# led_cube_4x4x8_v1.net
KiCad netlist of a schematic drawn in EAGLE
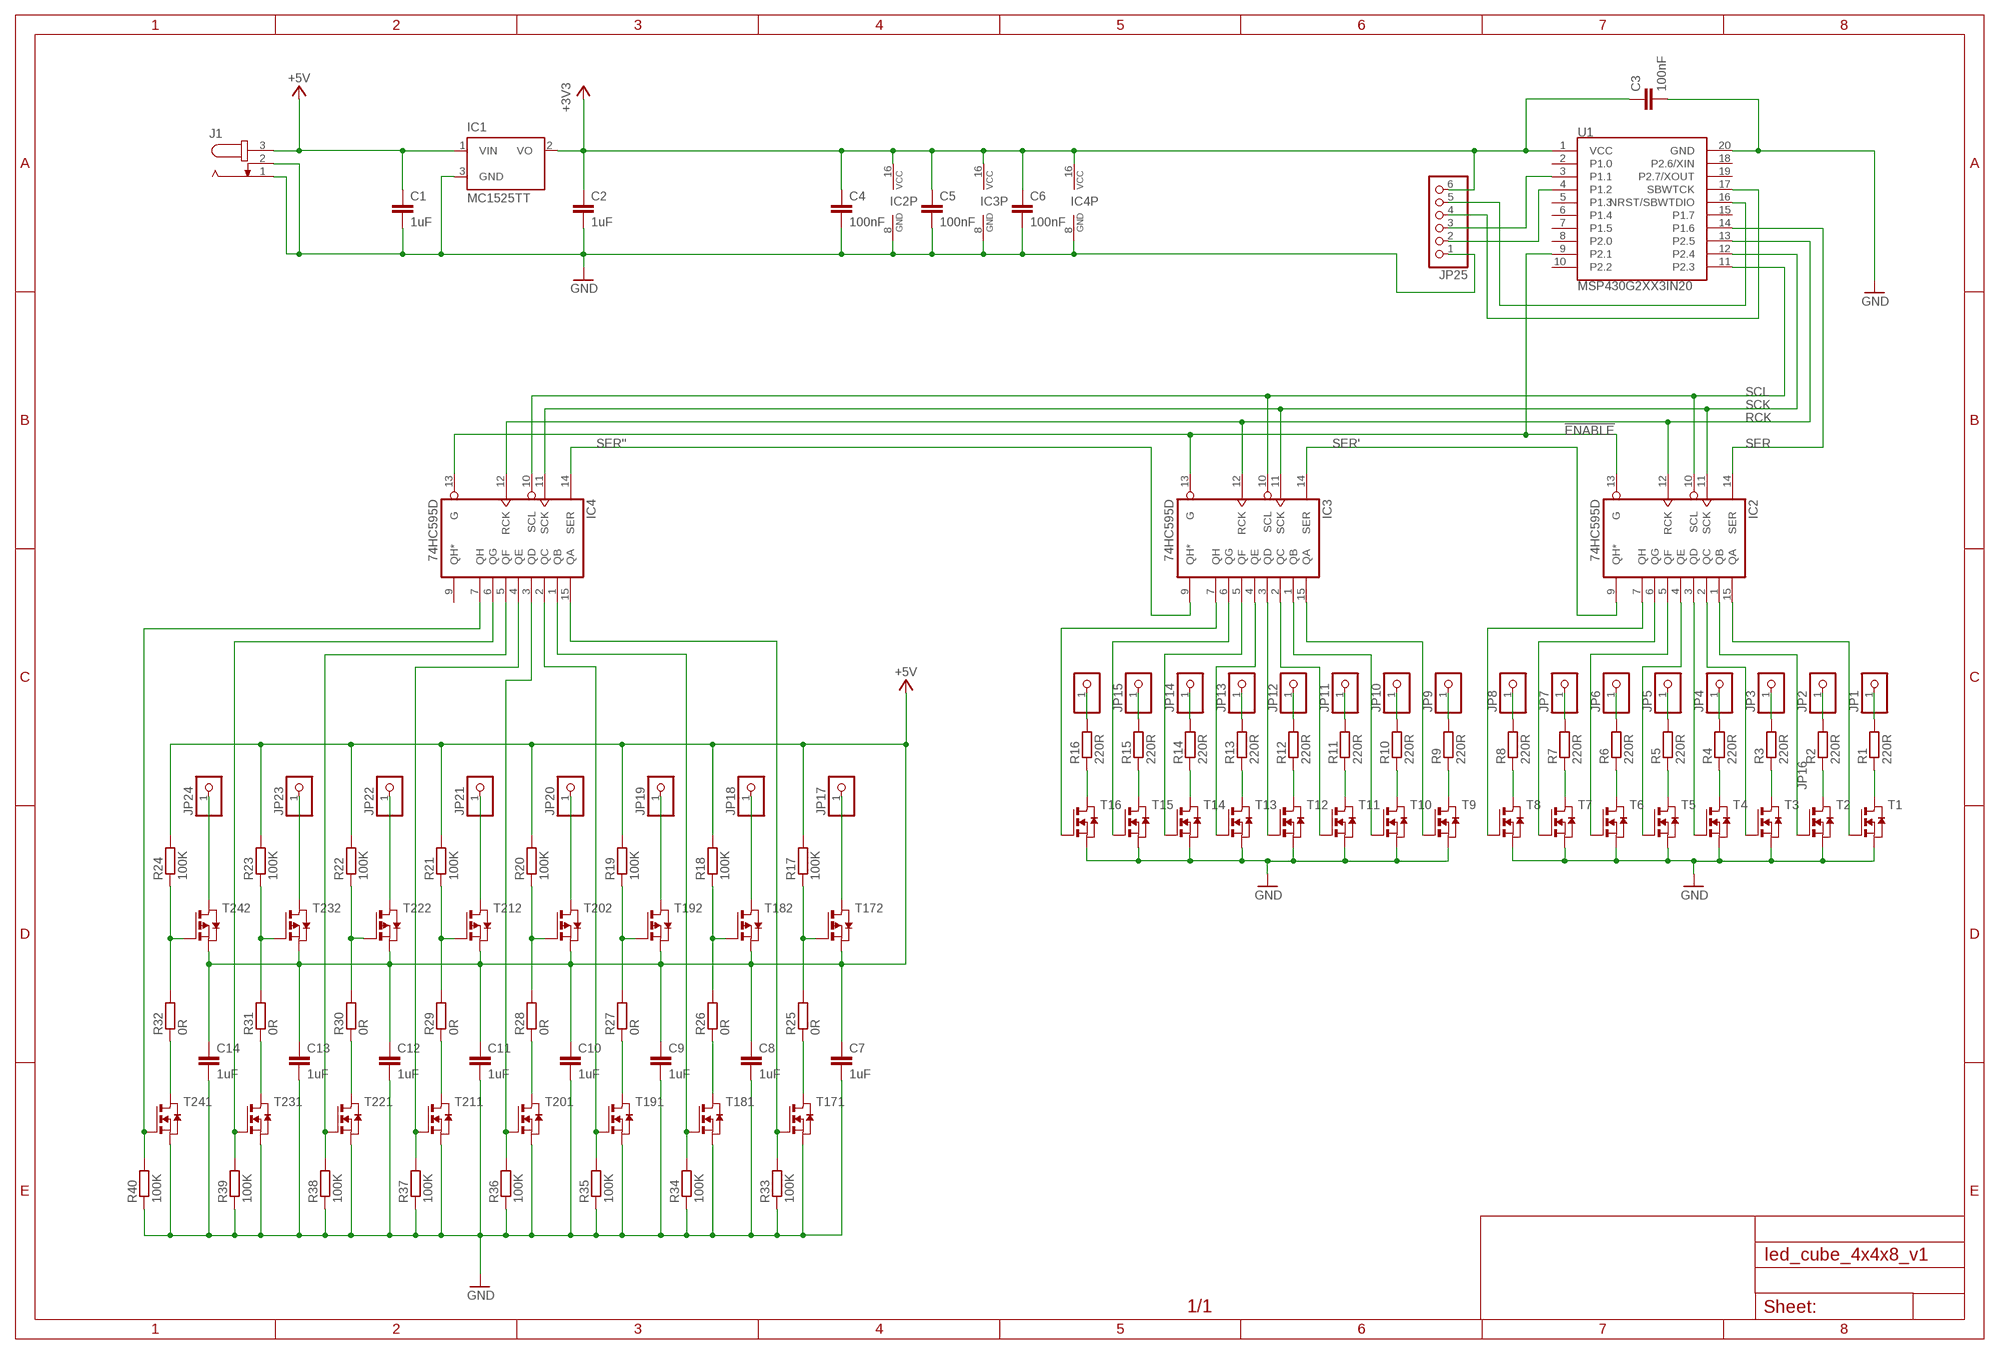
[diagram p0: schematic, sheet 1]

(export (version "E")
  (design (tool "Eeschema 10.0.6"))
  (components
    (comp (ref "C1")
      (value "1uF")
      (footprint "eagle-import:C0603")
      (libsource (lib "eagle-import") (part "C-EUC0603"))
    )
    (comp (ref "C2")
      (value "1uF")
      (footprint "eagle-import:C0603")
      (libsource (lib "eagle-import") (part "C-EUC0603"))
    )
    (comp (ref "C3")
      (value "100nF")
      (footprint "eagle-import:C0603")
      (libsource (lib "eagle-import") (part "C-EUC0603"))
    )
    (comp (ref "C4")
      (value "100nF")
      (footprint "eagle-import:C0603")
      (libsource (lib "eagle-import") (part "C-EUC0603"))
    )
    (comp (ref "C5")
      (value "100nF")
      (footprint "eagle-import:C0603")
      (libsource (lib "eagle-import") (part "C-EUC0603"))
    )
    (comp (ref "C6")
      (value "100nF")
      (footprint "eagle-import:C0603")
      (libsource (lib "eagle-import") (part "C-EUC0603"))
    )
    (comp (ref "C7")
      (value "1uF")
      (footprint "eagle-import:C0603")
      (libsource (lib "eagle-import") (part "C-EUC0603"))
    )
    (comp (ref "C8")
      (value "1uF")
      (footprint "eagle-import:C0603")
      (libsource (lib "eagle-import") (part "C-EUC0603"))
    )
    (comp (ref "C9")
      (value "1uF")
      (footprint "eagle-import:C0603")
      (libsource (lib "eagle-import") (part "C-EUC0603"))
    )
    (comp (ref "C10")
      (value "1uF")
      (footprint "eagle-import:C0603")
      (libsource (lib "eagle-import") (part "C-EUC0603"))
    )
    (comp (ref "C11")
      (value "1uF")
      (footprint "eagle-import:C0603")
      (libsource (lib "eagle-import") (part "C-EUC0603"))
    )
    (comp (ref "C12")
      (value "1uF")
      (footprint "eagle-import:C0603")
      (libsource (lib "eagle-import") (part "C-EUC0603"))
    )
    (comp (ref "C13")
      (value "1uF")
      (footprint "eagle-import:C0603")
      (libsource (lib "eagle-import") (part "C-EUC0603"))
    )
    (comp (ref "C14")
      (value "1uF")
      (footprint "eagle-import:C0603")
      (libsource (lib "eagle-import") (part "C-EUC0603"))
    )
    (comp (ref "IC1")
      (value "MC1525TT")
      (footprint "eagle-import:SOT23")
      (libsource (lib "eagle-import") (part "MC15TT25"))
    )
    (comp (ref "IC2")
      (value "74HC595D")
      (footprint "eagle-import:SO16")
      (libsource (lib "eagle-import") (part "74595DHC"))
    )
    (comp (ref "IC3")
      (value "74HC595D")
      (footprint "eagle-import:SO16")
      (libsource (lib "eagle-import") (part "74595DHC"))
    )
    (comp (ref "IC4")
      (value "74HC595D")
      (footprint "eagle-import:SO16")
      (libsource (lib "eagle-import") (part "74595DHC"))
    )
    (comp (ref "J1")
      (value "JACK-PLUG0")
      (footprint "eagle-import:SPC4077")
      (libsource (lib "eagle-import") (part "JACK-PLUG0"))
    )
    (comp (ref "JP1")
      (value "PINHD-1X1")
      (footprint "eagle-import:1X01")
      (libsource (lib "eagle-import") (part "PINHD-1X1"))
    )
    (comp (ref "JP2")
      (value "PINHD-1X1")
      (footprint "eagle-import:1X01")
      (libsource (lib "eagle-import") (part "PINHD-1X1"))
    )
    (comp (ref "JP3")
      (value "PINHD-1X1")
      (footprint "eagle-import:1X01")
      (libsource (lib "eagle-import") (part "PINHD-1X1"))
    )
    (comp (ref "JP4")
      (value "PINHD-1X1")
      (footprint "eagle-import:1X01")
      (libsource (lib "eagle-import") (part "PINHD-1X1"))
    )
    (comp (ref "JP5")
      (value "PINHD-1X1")
      (footprint "eagle-import:1X01")
      (libsource (lib "eagle-import") (part "PINHD-1X1"))
    )
    (comp (ref "JP6")
      (value "PINHD-1X1")
      (footprint "eagle-import:1X01")
      (libsource (lib "eagle-import") (part "PINHD-1X1"))
    )
    (comp (ref "JP7")
      (value "PINHD-1X1")
      (footprint "eagle-import:1X01")
      (libsource (lib "eagle-import") (part "PINHD-1X1"))
    )
    (comp (ref "JP8")
      (value "PINHD-1X1")
      (footprint "eagle-import:1X01")
      (libsource (lib "eagle-import") (part "PINHD-1X1"))
    )
    (comp (ref "JP9")
      (value "PINHD-1X1")
      (footprint "eagle-import:1X01")
      (libsource (lib "eagle-import") (part "PINHD-1X1"))
    )
    (comp (ref "JP10")
      (value "PINHD-1X1")
      (footprint "eagle-import:1X01")
      (libsource (lib "eagle-import") (part "PINHD-1X1"))
    )
    (comp (ref "JP11")
      (value "PINHD-1X1")
      (footprint "eagle-import:1X01")
      (libsource (lib "eagle-import") (part "PINHD-1X1"))
    )
    (comp (ref "JP12")
      (value "PINHD-1X1")
      (footprint "eagle-import:1X01")
      (libsource (lib "eagle-import") (part "PINHD-1X1"))
    )
    (comp (ref "JP13")
      (value "PINHD-1X1")
      (footprint "eagle-import:1X01")
      (libsource (lib "eagle-import") (part "PINHD-1X1"))
    )
    (comp (ref "JP14")
      (value "PINHD-1X1")
      (footprint "eagle-import:1X01")
      (libsource (lib "eagle-import") (part "PINHD-1X1"))
    )
    (comp (ref "JP15")
      (value "PINHD-1X1")
      (footprint "eagle-import:1X01")
      (libsource (lib "eagle-import") (part "PINHD-1X1"))
    )
    (comp (ref "JP16")
      (value "PINHD-1X1")
      (footprint "eagle-import:1X01")
      (libsource (lib "eagle-import") (part "PINHD-1X1"))
    )
    (comp (ref "JP17")
      (value "PINHD-1X1")
      (footprint "eagle-import:1X01")
      (libsource (lib "eagle-import") (part "PINHD-1X1"))
    )
    (comp (ref "JP18")
      (value "PINHD-1X1")
      (footprint "eagle-import:1X01")
      (libsource (lib "eagle-import") (part "PINHD-1X1"))
    )
    (comp (ref "JP19")
      (value "PINHD-1X1")
      (footprint "eagle-import:1X01")
      (libsource (lib "eagle-import") (part "PINHD-1X1"))
    )
    (comp (ref "JP20")
      (value "PINHD-1X1")
      (footprint "eagle-import:1X01")
      (libsource (lib "eagle-import") (part "PINHD-1X1"))
    )
    (comp (ref "JP21")
      (value "PINHD-1X1")
      (footprint "eagle-import:1X01")
      (libsource (lib "eagle-import") (part "PINHD-1X1"))
    )
    (comp (ref "JP22")
      (value "PINHD-1X1")
      (footprint "eagle-import:1X01")
      (libsource (lib "eagle-import") (part "PINHD-1X1"))
    )
    (comp (ref "JP23")
      (value "PINHD-1X1")
      (footprint "eagle-import:1X01")
      (libsource (lib "eagle-import") (part "PINHD-1X1"))
    )
    (comp (ref "JP24")
      (value "PINHD-1X1")
      (footprint "eagle-import:1X01")
      (libsource (lib "eagle-import") (part "PINHD-1X1"))
    )
    (comp (ref "JP25")
      (value "PINHD-1X6")
      (footprint "eagle-import:1X06")
      (libsource (lib "eagle-import") (part "PINHD-1X6"))
    )
    (comp (ref "R1")
      (value "220R")
      (footprint "eagle-import:R0603")
      (libsource (lib "eagle-import") (part "R-EU_R0603"))
    )
    (comp (ref "R2")
      (value "220R")
      (footprint "eagle-import:R0603")
      (libsource (lib "eagle-import") (part "R-EU_R0603"))
    )
    (comp (ref "R3")
      (value "220R")
      (footprint "eagle-import:R0603")
      (libsource (lib "eagle-import") (part "R-EU_R0603"))
    )
    (comp (ref "R4")
      (value "220R")
      (footprint "eagle-import:R0603")
      (libsource (lib "eagle-import") (part "R-EU_R0603"))
    )
    (comp (ref "R5")
      (value "220R")
      (footprint "eagle-import:R0603")
      (libsource (lib "eagle-import") (part "R-EU_R0603"))
    )
    (comp (ref "R6")
      (value "220R")
      (footprint "eagle-import:R0603")
      (libsource (lib "eagle-import") (part "R-EU_R0603"))
    )
    (comp (ref "R7")
      (value "220R")
      (footprint "eagle-import:R0603")
      (libsource (lib "eagle-import") (part "R-EU_R0603"))
    )
    (comp (ref "R8")
      (value "220R")
      (footprint "eagle-import:R0603")
      (libsource (lib "eagle-import") (part "R-EU_R0603"))
    )
    (comp (ref "R9")
      (value "220R")
      (footprint "eagle-import:R0603")
      (libsource (lib "eagle-import") (part "R-EU_R0603"))
    )
    (comp (ref "R10")
      (value "220R")
      (footprint "eagle-import:R0603")
      (libsource (lib "eagle-import") (part "R-EU_R0603"))
    )
    (comp (ref "R11")
      (value "220R")
      (footprint "eagle-import:R0603")
      (libsource (lib "eagle-import") (part "R-EU_R0603"))
    )
    (comp (ref "R12")
      (value "220R")
      (footprint "eagle-import:R0603")
      (libsource (lib "eagle-import") (part "R-EU_R0603"))
    )
    (comp (ref "R13")
      (value "220R")
      (footprint "eagle-import:R0603")
      (libsource (lib "eagle-import") (part "R-EU_R0603"))
    )
    (comp (ref "R14")
      (value "220R")
      (footprint "eagle-import:R0603")
      (libsource (lib "eagle-import") (part "R-EU_R0603"))
    )
    (comp (ref "R15")
      (value "220R")
      (footprint "eagle-import:R0603")
      (libsource (lib "eagle-import") (part "R-EU_R0603"))
    )
    (comp (ref "R16")
      (value "220R")
      (footprint "eagle-import:R0603")
      (libsource (lib "eagle-import") (part "R-EU_R0603"))
    )
    (comp (ref "R17")
      (value "100K")
      (footprint "eagle-import:R0603")
      (libsource (lib "eagle-import") (part "R-EU_R0603"))
    )
    (comp (ref "R18")
      (value "100K")
      (footprint "eagle-import:R0603")
      (libsource (lib "eagle-import") (part "R-EU_R0603"))
    )
    (comp (ref "R19")
      (value "100K")
      (footprint "eagle-import:R0603")
      (libsource (lib "eagle-import") (part "R-EU_R0603"))
    )
    (comp (ref "R20")
      (value "100K")
      (footprint "eagle-import:R0603")
      (libsource (lib "eagle-import") (part "R-EU_R0603"))
    )
    (comp (ref "R21")
      (value "100K")
      (footprint "eagle-import:R0603")
      (libsource (lib "eagle-import") (part "R-EU_R0603"))
    )
    (comp (ref "R22")
      (value "100K")
      (footprint "eagle-import:R0603")
      (libsource (lib "eagle-import") (part "R-EU_R0603"))
    )
    (comp (ref "R23")
      (value "100K")
      (footprint "eagle-import:R0603")
      (libsource (lib "eagle-import") (part "R-EU_R0603"))
    )
    (comp (ref "R24")
      (value "100K")
      (footprint "eagle-import:R0603")
      (libsource (lib "eagle-import") (part "R-EU_R0603"))
    )
    (comp (ref "R25")
      (value "0R")
      (footprint "eagle-import:R0603")
      (libsource (lib "eagle-import") (part "R-EU_R0603"))
    )
    (comp (ref "R26")
      (value "0R")
      (footprint "eagle-import:R0603")
      (libsource (lib "eagle-import") (part "R-EU_R0603"))
    )
    (comp (ref "R27")
      (value "0R")
      (footprint "eagle-import:R0603")
      (libsource (lib "eagle-import") (part "R-EU_R0603"))
    )
    (comp (ref "R28")
      (value "0R")
      (footprint "eagle-import:R0603")
      (libsource (lib "eagle-import") (part "R-EU_R0603"))
    )
    (comp (ref "R29")
      (value "0R")
      (footprint "eagle-import:R0603")
      (libsource (lib "eagle-import") (part "R-EU_R0603"))
    )
    (comp (ref "R30")
      (value "0R")
      (footprint "eagle-import:R0603")
      (libsource (lib "eagle-import") (part "R-EU_R0603"))
    )
    (comp (ref "R31")
      (value "0R")
      (footprint "eagle-import:R0603")
      (libsource (lib "eagle-import") (part "R-EU_R0603"))
    )
    (comp (ref "R32")
      (value "0R")
      (footprint "eagle-import:R0603")
      (libsource (lib "eagle-import") (part "R-EU_R0603"))
    )
    (comp (ref "R33")
      (value "100K")
      (footprint "eagle-import:R0603")
      (libsource (lib "eagle-import") (part "R-EU_R0603"))
    )
    (comp (ref "R34")
      (value "100K")
      (footprint "eagle-import:R0603")
      (libsource (lib "eagle-import") (part "R-EU_R0603"))
    )
    (comp (ref "R35")
      (value "100K")
      (footprint "eagle-import:R0603")
      (libsource (lib "eagle-import") (part "R-EU_R0603"))
    )
    (comp (ref "R36")
      (value "100K")
      (footprint "eagle-import:R0603")
      (libsource (lib "eagle-import") (part "R-EU_R0603"))
    )
    (comp (ref "R37")
      (value "100K")
      (footprint "eagle-import:R0603")
      (libsource (lib "eagle-import") (part "R-EU_R0603"))
    )
    (comp (ref "R38")
      (value "100K")
      (footprint "eagle-import:R0603")
      (libsource (lib "eagle-import") (part "R-EU_R0603"))
    )
    (comp (ref "R39")
      (value "100K")
      (footprint "eagle-import:R0603")
      (libsource (lib "eagle-import") (part "R-EU_R0603"))
    )
    (comp (ref "R40")
      (value "100K")
      (footprint "eagle-import:R0603")
      (libsource (lib "eagle-import") (part "R-EU_R0603"))
    )
    (comp (ref "T1")
      (value "NMOSSOT23")
      (footprint "eagle-import:SOT-23")
      (libsource (lib "eagle-import") (part "NMOSSOT23"))
    )
    (comp (ref "T2")
      (value "NMOSSOT23")
      (footprint "eagle-import:SOT-23")
      (libsource (lib "eagle-import") (part "NMOSSOT23"))
    )
    (comp (ref "T3")
      (value "NMOSSOT23")
      (footprint "eagle-import:SOT-23")
      (libsource (lib "eagle-import") (part "NMOSSOT23"))
    )
    (comp (ref "T4")
      (value "NMOSSOT23")
      (footprint "eagle-import:SOT-23")
      (libsource (lib "eagle-import") (part "NMOSSOT23"))
    )
    (comp (ref "T5")
      (value "NMOSSOT23")
      (footprint "eagle-import:SOT-23")
      (libsource (lib "eagle-import") (part "NMOSSOT23"))
    )
    (comp (ref "T6")
      (value "NMOSSOT23")
      (footprint "eagle-import:SOT-23")
      (libsource (lib "eagle-import") (part "NMOSSOT23"))
    )
    (comp (ref "T7")
      (value "NMOSSOT23")
      (footprint "eagle-import:SOT-23")
      (libsource (lib "eagle-import") (part "NMOSSOT23"))
    )
    (comp (ref "T8")
      (value "NMOSSOT23")
      (footprint "eagle-import:SOT-23")
      (libsource (lib "eagle-import") (part "NMOSSOT23"))
    )
    (comp (ref "T9")
      (value "NMOSSOT23")
      (footprint "eagle-import:SOT-23")
      (libsource (lib "eagle-import") (part "NMOSSOT23"))
    )
    (comp (ref "T10")
      (value "NMOSSOT23")
      (footprint "eagle-import:SOT-23")
      (libsource (lib "eagle-import") (part "NMOSSOT23"))
    )
    (comp (ref "T11")
      (value "NMOSSOT23")
      (footprint "eagle-import:SOT-23")
      (libsource (lib "eagle-import") (part "NMOSSOT23"))
    )
    (comp (ref "T12")
      (value "NMOSSOT23")
      (footprint "eagle-import:SOT-23")
      (libsource (lib "eagle-import") (part "NMOSSOT23"))
    )
    (comp (ref "T13")
      (value "NMOSSOT23")
      (footprint "eagle-import:SOT-23")
      (libsource (lib "eagle-import") (part "NMOSSOT23"))
    )
    (comp (ref "T14")
      (value "NMOSSOT23")
      (footprint "eagle-import:SOT-23")
      (libsource (lib "eagle-import") (part "NMOSSOT23"))
    )
    (comp (ref "T15")
      (value "NMOSSOT23")
      (footprint "eagle-import:SOT-23")
      (libsource (lib "eagle-import") (part "NMOSSOT23"))
    )
    (comp (ref "T16")
      (value "NMOSSOT23")
      (footprint "eagle-import:SOT-23")
      (libsource (lib "eagle-import") (part "NMOSSOT23"))
    )
    (comp (ref "T17")
      (value "PN_MOSFET-SOT23-6")
      (footprint "eagle-import:SOT23-6")
      (libsource (lib "eagle-import") (part "PN_MOSFET-SOT23-6"))
    )
    (comp (ref "T18")
      (value "PN_MOSFET-SOT23-6")
      (footprint "eagle-import:SOT23-6")
      (libsource (lib "eagle-import") (part "PN_MOSFET-SOT23-6"))
    )
    (comp (ref "T19")
      (value "PN_MOSFET-SOT23-6")
      (footprint "eagle-import:SOT23-6")
      (libsource (lib "eagle-import") (part "PN_MOSFET-SOT23-6"))
    )
    (comp (ref "T20")
      (value "PN_MOSFET-SOT23-6")
      (footprint "eagle-import:SOT23-6")
      (libsource (lib "eagle-import") (part "PN_MOSFET-SOT23-6"))
    )
    (comp (ref "T21")
      (value "PN_MOSFET-SOT23-6")
      (footprint "eagle-import:SOT23-6")
      (libsource (lib "eagle-import") (part "PN_MOSFET-SOT23-6"))
    )
    (comp (ref "T22")
      (value "PN_MOSFET-SOT23-6")
      (footprint "eagle-import:SOT23-6")
      (libsource (lib "eagle-import") (part "PN_MOSFET-SOT23-6"))
    )
    (comp (ref "T23")
      (value "PN_MOSFET-SOT23-6")
      (footprint "eagle-import:SOT23-6")
      (libsource (lib "eagle-import") (part "PN_MOSFET-SOT23-6"))
    )
    (comp (ref "T24")
      (value "PN_MOSFET-SOT23-6")
      (footprint "eagle-import:SOT23-6")
      (libsource (lib "eagle-import") (part "PN_MOSFET-SOT23-6"))
    )
    (comp (ref "U1")
      (value "MSP430G2XX3IN20")
      (footprint "eagle-import:DIL20")
      (libsource (lib "eagle-import") (part "MSP430G2XX3IN20"))
    )
  )
  (nets
    (net (code "1") (name "+3V3") (class "Default")
      (node (ref "C2") (pin "1") (pinfunction "1_1") (pintype "passive"))
      (node (ref "C3") (pin "1") (pinfunction "1_1") (pintype "passive"))
      (node (ref "C4") (pin "1") (pinfunction "1_1") (pintype "passive"))
      (node (ref "C5") (pin "1") (pinfunction "1_1") (pintype "passive"))
      (node (ref "C6") (pin "1") (pinfunction "1_1") (pintype "passive"))
      (node (ref "IC1") (pin "2") (pinfunction "VO_2") (pintype "output"))
      (node (ref "IC2") (pin "16") (pinfunction "VCC_16") (pintype "power_in"))
      (node (ref "IC3") (pin "16") (pinfunction "VCC_16") (pintype "power_in"))
      (node (ref "IC4") (pin "16") (pinfunction "VCC_16") (pintype "power_in"))
      (node (ref "JP25") (pin "6") (pinfunction "6_6") (pintype "passive"))
      (node (ref "U1") (pin "1") (pinfunction "VCC_1") (pintype "bidirectional"))
    )
    (net (code "2") (name "+5V") (class "Default")
      (node (ref "C1") (pin "1") (pinfunction "1_1") (pintype "passive"))
      (node (ref "C10") (pin "1") (pinfunction "1_1") (pintype "passive"))
      (node (ref "C11") (pin "1") (pinfunction "1_1") (pintype "passive"))
      (node (ref "C12") (pin "1") (pinfunction "1_1") (pintype "passive"))
      (node (ref "C13") (pin "1") (pinfunction "1_1") (pintype "passive"))
      (node (ref "C14") (pin "1") (pinfunction "1_1") (pintype "passive"))
      (node (ref "C7") (pin "1") (pinfunction "1_1") (pintype "passive"))
      (node (ref "C8") (pin "1") (pinfunction "1_1") (pintype "passive"))
      (node (ref "C9") (pin "1") (pinfunction "1_1") (pintype "passive"))
      (node (ref "IC1") (pin "1") (pinfunction "VIN_1") (pintype "input"))
      (node (ref "J1") (pin "3") (pinfunction "3_3") (pintype "passive"))
      (node (ref "R17") (pin "2") (pinfunction "2_2") (pintype "passive"))
      (node (ref "R18") (pin "2") (pinfunction "2_2") (pintype "passive"))
      (node (ref "R19") (pin "2") (pinfunction "2_2") (pintype "passive"))
      (node (ref "R20") (pin "2") (pinfunction "2_2") (pintype "passive"))
      (node (ref "R21") (pin "2") (pinfunction "2_2") (pintype "passive"))
      (node (ref "R22") (pin "2") (pinfunction "2_2") (pintype "passive"))
      (node (ref "R23") (pin "2") (pinfunction "2_2") (pintype "passive"))
      (node (ref "R24") (pin "2") (pinfunction "2_2") (pintype "passive"))
      (node (ref "T17") (pin "2") (pinfunction "S_2") (pintype "passive"))
      (node (ref "T18") (pin "2") (pinfunction "S_2") (pintype "passive"))
      (node (ref "T19") (pin "2") (pinfunction "S_2") (pintype "passive"))
      (node (ref "T20") (pin "2") (pinfunction "S_2") (pintype "passive"))
      (node (ref "T21") (pin "2") (pinfunction "S_2") (pintype "passive"))
      (node (ref "T22") (pin "2") (pinfunction "S_2") (pintype "passive"))
      (node (ref "T23") (pin "2") (pinfunction "S_2") (pintype "passive"))
      (node (ref "T24") (pin "2") (pinfunction "S_2") (pintype "passive"))
    )
    (net (code "3") (name "/RCK") (class "Default")
      (node (ref "IC2") (pin "12") (pinfunction "RCK_12") (pintype "input"))
      (node (ref "IC3") (pin "12") (pinfunction "RCK_12") (pintype "input"))
      (node (ref "IC4") (pin "12") (pinfunction "RCK_12") (pintype "input"))
      (node (ref "U1") (pin "13") (pinfunction "P2.5_13") (pintype "bidirectional"))
    )
    (net (code "4") (name "/SCK") (class "Default")
      (node (ref "IC2") (pin "11") (pinfunction "SCK_11") (pintype "input"))
      (node (ref "IC3") (pin "11") (pinfunction "SCK_11") (pintype "input"))
      (node (ref "IC4") (pin "11") (pinfunction "SCK_11") (pintype "input"))
      (node (ref "U1") (pin "12") (pinfunction "P2.4_12") (pintype "bidirectional"))
    )
    (net (code "5") (name "/SCL") (class "Default")
      (node (ref "IC2") (pin "10") (pinfunction "SCL_10") (pintype "input"))
      (node (ref "IC3") (pin "10") (pinfunction "SCL_10") (pintype "input"))
      (node (ref "IC4") (pin "10") (pinfunction "SCL_10") (pintype "input"))
      (node (ref "U1") (pin "11") (pinfunction "P2.3_11") (pintype "bidirectional"))
    )
    (net (code "6") (name "/SER") (class "Default")
      (node (ref "IC2") (pin "14") (pinfunction "SER_14") (pintype "input"))
      (node (ref "U1") (pin "14") (pinfunction "P1.6_14") (pintype "bidirectional"))
    )
    (net (code "7") (name "/SER'") (class "Default")
      (node (ref "IC2") (pin "9") (pinfunction "QH*_9") (pintype "tri_state"))
      (node (ref "IC3") (pin "14") (pinfunction "SER_14") (pintype "input"))
    )
    (net (code "8") (name "/SER''") (class "Default")
      (node (ref "IC3") (pin "9") (pinfunction "QH*_9") (pintype "tri_state"))
      (node (ref "IC4") (pin "14") (pinfunction "SER_14") (pintype "input"))
    )
    (net (code "9") (name "/~{ENABLE}") (class "Default")
      (node (ref "IC2") (pin "13") (pinfunction "G_13") (pintype "input"))
      (node (ref "IC3") (pin "13") (pinfunction "G_13") (pintype "input"))
      (node (ref "IC4") (pin "13") (pinfunction "G_13") (pintype "input"))
      (node (ref "U1") (pin "9") (pinfunction "P2.1_9") (pintype "bidirectional"))
    )
    (net (code "10") (name "GND") (class "Default")
      (node (ref "C1") (pin "2") (pinfunction "2_2") (pintype "passive"))
      (node (ref "C10") (pin "2") (pinfunction "2_2") (pintype "passive"))
      (node (ref "C11") (pin "2") (pinfunction "2_2") (pintype "passive"))
      (node (ref "C12") (pin "2") (pinfunction "2_2") (pintype "passive"))
      (node (ref "C13") (pin "2") (pinfunction "2_2") (pintype "passive"))
      (node (ref "C14") (pin "2") (pinfunction "2_2") (pintype "passive"))
      (node (ref "C2") (pin "2") (pinfunction "2_2") (pintype "passive"))
      (node (ref "C3") (pin "2") (pinfunction "2_2") (pintype "passive"))
      (node (ref "C4") (pin "2") (pinfunction "2_2") (pintype "passive"))
      (node (ref "C5") (pin "2") (pinfunction "2_2") (pintype "passive"))
      (node (ref "C6") (pin "2") (pinfunction "2_2") (pintype "passive"))
      (node (ref "C7") (pin "2") (pinfunction "2_2") (pintype "passive"))
      (node (ref "C8") (pin "2") (pinfunction "2_2") (pintype "passive"))
      (node (ref "C9") (pin "2") (pinfunction "2_2") (pintype "passive"))
      (node (ref "IC1") (pin "3") (pinfunction "GND_3") (pintype "passive"))
      (node (ref "IC2") (pin "8") (pinfunction "GND_8") (pintype "power_in"))
      (node (ref "IC3") (pin "8") (pinfunction "GND_8") (pintype "power_in"))
      (node (ref "IC4") (pin "8") (pinfunction "GND_8") (pintype "power_in"))
      (node (ref "J1") (pin "1") (pinfunction "1_1") (pintype "passive"))
      (node (ref "J1") (pin "2") (pinfunction "2_2") (pintype "passive"))
      (node (ref "JP25") (pin "1") (pinfunction "1_1") (pintype "passive"))
      (node (ref "R33") (pin "1") (pinfunction "1_1") (pintype "passive"))
      (node (ref "R34") (pin "1") (pinfunction "1_1") (pintype "passive"))
      (node (ref "R35") (pin "1") (pinfunction "1_1") (pintype "passive"))
      (node (ref "R36") (pin "1") (pinfunction "1_1") (pintype "passive"))
      (node (ref "R37") (pin "1") (pinfunction "1_1") (pintype "passive"))
      (node (ref "R38") (pin "1") (pinfunction "1_1") (pintype "passive"))
      (node (ref "R39") (pin "1") (pinfunction "1_1") (pintype "passive"))
      (node (ref "R40") (pin "1") (pinfunction "1_1") (pintype "passive"))
      (node (ref "T1") (pin "2") (pinfunction "S_2") (pintype "passive"))
      (node (ref "T10") (pin "2") (pinfunction "S_2") (pintype "passive"))
      (node (ref "T11") (pin "2") (pinfunction "S_2") (pintype "passive"))
      (node (ref "T12") (pin "2") (pinfunction "S_2") (pintype "passive"))
      (node (ref "T13") (pin "2") (pinfunction "S_2") (pintype "passive"))
      (node (ref "T14") (pin "2") (pinfunction "S_2") (pintype "passive"))
      (node (ref "T15") (pin "2") (pinfunction "S_2") (pintype "passive"))
      (node (ref "T16") (pin "2") (pinfunction "S_2") (pintype "passive"))
      (node (ref "T17") (pin "5") (pinfunction "S_5") (pintype "passive"))
      (node (ref "T18") (pin "5") (pinfunction "S_5") (pintype "passive"))
      (node (ref "T19") (pin "5") (pinfunction "S_5") (pintype "passive"))
      (node (ref "T2") (pin "2") (pinfunction "S_2") (pintype "passive"))
      (node (ref "T20") (pin "5") (pinfunction "S_5") (pintype "passive"))
      (node (ref "T21") (pin "5") (pinfunction "S_5") (pintype "passive"))
      (node (ref "T22") (pin "5") (pinfunction "S_5") (pintype "passive"))
      (node (ref "T23") (pin "5") (pinfunction "S_5") (pintype "passive"))
      (node (ref "T24") (pin "5") (pinfunction "S_5") (pintype "passive"))
      (node (ref "T3") (pin "2") (pinfunction "S_2") (pintype "passive"))
      (node (ref "T4") (pin "2") (pinfunction "S_2") (pintype "passive"))
      (node (ref "T5") (pin "2") (pinfunction "S_2") (pintype "passive"))
      (node (ref "T6") (pin "2") (pinfunction "S_2") (pintype "passive"))
      (node (ref "T7") (pin "2") (pinfunction "S_2") (pintype "passive"))
      (node (ref "T8") (pin "2") (pinfunction "S_2") (pintype "passive"))
      (node (ref "T9") (pin "2") (pinfunction "S_2") (pintype "passive"))
      (node (ref "U1") (pin "20") (pinfunction "GND_20") (pintype "bidirectional"))
    )
    (net (code "11") (name "Net-(IC2A-QA)") (class "Default")
      (node (ref "IC2") (pin "15") (pinfunction "QA_15") (pintype "tri_state"))
      (node (ref "T1") (pin "3") (pinfunction "G_3") (pintype "passive"))
    )
    (net (code "12") (name "Net-(IC2A-QB)") (class "Default")
      (node (ref "IC2") (pin "1") (pinfunction "QB_1") (pintype "tri_state"))
      (node (ref "T2") (pin "3") (pinfunction "G_3") (pintype "passive"))
    )
    (net (code "13") (name "Net-(IC2A-QC)") (class "Default")
      (node (ref "IC2") (pin "2") (pinfunction "QC_2") (pintype "tri_state"))
      (node (ref "T3") (pin "3") (pinfunction "G_3") (pintype "passive"))
    )
    (net (code "14") (name "Net-(IC2A-QD)") (class "Default")
      (node (ref "IC2") (pin "3") (pinfunction "QD_3") (pintype "tri_state"))
      (node (ref "T4") (pin "3") (pinfunction "G_3") (pintype "passive"))
    )
    (net (code "15") (name "Net-(IC2A-QE)") (class "Default")
      (node (ref "IC2") (pin "4") (pinfunction "QE_4") (pintype "tri_state"))
      (node (ref "T5") (pin "3") (pinfunction "G_3") (pintype "passive"))
    )
    (net (code "16") (name "Net-(IC2A-QF)") (class "Default")
      (node (ref "IC2") (pin "5") (pinfunction "QF_5") (pintype "tri_state"))
      (node (ref "T6") (pin "3") (pinfunction "G_3") (pintype "passive"))
    )
    (net (code "17") (name "Net-(IC2A-QG)") (class "Default")
      (node (ref "IC2") (pin "6") (pinfunction "QG_6") (pintype "tri_state"))
      (node (ref "T7") (pin "3") (pinfunction "G_3") (pintype "passive"))
    )
    (net (code "18") (name "Net-(IC2A-QH)") (class "Default")
      (node (ref "IC2") (pin "7") (pinfunction "QH_7") (pintype "tri_state"))
      (node (ref "T8") (pin "3") (pinfunction "G_3") (pintype "passive"))
    )
    (net (code "19") (name "Net-(IC3A-QA)") (class "Default")
      (node (ref "IC3") (pin "15") (pinfunction "QA_15") (pintype "tri_state"))
      (node (ref "T9") (pin "3") (pinfunction "G_3") (pintype "passive"))
    )
    (net (code "20") (name "Net-(IC3A-QB)") (class "Default")
      (node (ref "IC3") (pin "1") (pinfunction "QB_1") (pintype "tri_state"))
      (node (ref "T10") (pin "3") (pinfunction "G_3") (pintype "passive"))
    )
    (net (code "21") (name "Net-(IC3A-QC)") (class "Default")
      (node (ref "IC3") (pin "2") (pinfunction "QC_2") (pintype "tri_state"))
      (node (ref "T11") (pin "3") (pinfunction "G_3") (pintype "passive"))
    )
    (net (code "22") (name "Net-(IC3A-QD)") (class "Default")
      (node (ref "IC3") (pin "3") (pinfunction "QD_3") (pintype "tri_state"))
      (node (ref "T12") (pin "3") (pinfunction "G_3") (pintype "passive"))
    )
    (net (code "23") (name "Net-(IC3A-QE)") (class "Default")
      (node (ref "IC3") (pin "4") (pinfunction "QE_4") (pintype "tri_state"))
      (node (ref "T13") (pin "3") (pinfunction "G_3") (pintype "passive"))
    )
    (net (code "24") (name "Net-(IC3A-QF)") (class "Default")
      (node (ref "IC3") (pin "5") (pinfunction "QF_5") (pintype "tri_state"))
      (node (ref "T14") (pin "3") (pinfunction "G_3") (pintype "passive"))
    )
    (net (code "25") (name "Net-(IC3A-QG)") (class "Default")
      (node (ref "IC3") (pin "6") (pinfunction "QG_6") (pintype "tri_state"))
      (node (ref "T15") (pin "3") (pinfunction "G_3") (pintype "passive"))
    )
    (net (code "26") (name "Net-(IC3A-QH)") (class "Default")
      (node (ref "IC3") (pin "7") (pinfunction "QH_7") (pintype "tri_state"))
      (node (ref "T16") (pin "3") (pinfunction "G_3") (pintype "passive"))
    )
    (net (code "27") (name "Net-(IC4A-QA)") (class "Default")
      (node (ref "IC4") (pin "15") (pinfunction "QA_15") (pintype "tri_state"))
      (node (ref "R33") (pin "2") (pinfunction "2_2") (pintype "passive"))
      (node (ref "T17") (pin "1") (pinfunction "G_1") (pintype "passive"))
    )
    (net (code "28") (name "Net-(IC4A-QB)") (class "Default")
      (node (ref "IC4") (pin "1") (pinfunction "QB_1") (pintype "tri_state"))
      (node (ref "R34") (pin "2") (pinfunction "2_2") (pintype "passive"))
      (node (ref "T18") (pin "1") (pinfunction "G_1") (pintype "passive"))
    )
    (net (code "29") (name "Net-(IC4A-QC)") (class "Default")
      (node (ref "IC4") (pin "2") (pinfunction "QC_2") (pintype "tri_state"))
      (node (ref "R35") (pin "2") (pinfunction "2_2") (pintype "passive"))
      (node (ref "T19") (pin "1") (pinfunction "G_1") (pintype "passive"))
    )
    (net (code "30") (name "Net-(IC4A-QD)") (class "Default")
      (node (ref "IC4") (pin "3") (pinfunction "QD_3") (pintype "tri_state"))
      (node (ref "R36") (pin "2") (pinfunction "2_2") (pintype "passive"))
      (node (ref "T20") (pin "1") (pinfunction "G_1") (pintype "passive"))
    )
    (net (code "31") (name "Net-(IC4A-QE)") (class "Default")
      (node (ref "IC4") (pin "4") (pinfunction "QE_4") (pintype "tri_state"))
      (node (ref "R37") (pin "2") (pinfunction "2_2") (pintype "passive"))
      (node (ref "T21") (pin "1") (pinfunction "G_1") (pintype "passive"))
    )
    (net (code "32") (name "Net-(IC4A-QF)") (class "Default")
      (node (ref "IC4") (pin "5") (pinfunction "QF_5") (pintype "tri_state"))
      (node (ref "R38") (pin "2") (pinfunction "2_2") (pintype "passive"))
      (node (ref "T22") (pin "1") (pinfunction "G_1") (pintype "passive"))
    )
    (net (code "33") (name "Net-(IC4A-QG)") (class "Default")
      (node (ref "IC4") (pin "6") (pinfunction "QG_6") (pintype "tri_state"))
      (node (ref "R39") (pin "2") (pinfunction "2_2") (pintype "passive"))
      (node (ref "T23") (pin "1") (pinfunction "G_1") (pintype "passive"))
    )
    (net (code "34") (name "Net-(IC4A-QH)") (class "Default")
      (node (ref "IC4") (pin "7") (pinfunction "QH_7") (pintype "tri_state"))
      (node (ref "R40") (pin "2") (pinfunction "2_2") (pintype "passive"))
      (node (ref "T24") (pin "1") (pinfunction "G_1") (pintype "passive"))
    )
    (net (code "35") (name "Net-(JP1-Pad1)") (class "Default")
      (node (ref "JP1") (pin "1") (pinfunction "1_1") (pintype "passive"))
      (node (ref "R1") (pin "2") (pinfunction "2_2") (pintype "passive"))
    )
    (net (code "36") (name "Net-(JP2-Pad1)") (class "Default")
      (node (ref "JP2") (pin "1") (pinfunction "1_1") (pintype "passive"))
      (node (ref "R2") (pin "2") (pinfunction "2_2") (pintype "passive"))
    )
    (net (code "37") (name "Net-(JP3-Pad1)") (class "Default")
      (node (ref "JP3") (pin "1") (pinfunction "1_1") (pintype "passive"))
      (node (ref "R3") (pin "2") (pinfunction "2_2") (pintype "passive"))
    )
    (net (code "38") (name "Net-(JP4-Pad1)") (class "Default")
      (node (ref "JP4") (pin "1") (pinfunction "1_1") (pintype "passive"))
      (node (ref "R4") (pin "2") (pinfunction "2_2") (pintype "passive"))
    )
    (net (code "39") (name "Net-(JP5-Pad1)") (class "Default")
      (node (ref "JP5") (pin "1") (pinfunction "1_1") (pintype "passive"))
      (node (ref "R5") (pin "2") (pinfunction "2_2") (pintype "passive"))
    )
    (net (code "40") (name "Net-(JP6-Pad1)") (class "Default")
      (node (ref "JP6") (pin "1") (pinfunction "1_1") (pintype "passive"))
      (node (ref "R6") (pin "2") (pinfunction "2_2") (pintype "passive"))
    )
    (net (code "41") (name "Net-(JP7-Pad1)") (class "Default")
      (node (ref "JP7") (pin "1") (pinfunction "1_1") (pintype "passive"))
      (node (ref "R7") (pin "2") (pinfunction "2_2") (pintype "passive"))
    )
    (net (code "42") (name "Net-(JP8-Pad1)") (class "Default")
      (node (ref "JP8") (pin "1") (pinfunction "1_1") (pintype "passive"))
      (node (ref "R8") (pin "2") (pinfunction "2_2") (pintype "passive"))
    )
    (net (code "43") (name "Net-(JP9-Pad1)") (class "Default")
      (node (ref "JP9") (pin "1") (pinfunction "1_1") (pintype "passive"))
      (node (ref "R9") (pin "2") (pinfunction "2_2") (pintype "passive"))
    )
    (net (code "44") (name "Net-(JP10-Pad1)") (class "Default")
      (node (ref "JP10") (pin "1") (pinfunction "1_1") (pintype "passive"))
      (node (ref "R10") (pin "2") (pinfunction "2_2") (pintype "passive"))
    )
    (net (code "45") (name "Net-(JP11-Pad1)") (class "Default")
      (node (ref "JP11") (pin "1") (pinfunction "1_1") (pintype "passive"))
      (node (ref "R11") (pin "2") (pinfunction "2_2") (pintype "passive"))
    )
    (net (code "46") (name "Net-(JP12-Pad1)") (class "Default")
      (node (ref "JP12") (pin "1") (pinfunction "1_1") (pintype "passive"))
      (node (ref "R12") (pin "2") (pinfunction "2_2") (pintype "passive"))
    )
    (net (code "47") (name "Net-(JP13-Pad1)") (class "Default")
      (node (ref "JP13") (pin "1") (pinfunction "1_1") (pintype "passive"))
      (node (ref "R13") (pin "2") (pinfunction "2_2") (pintype "passive"))
    )
    (net (code "48") (name "Net-(JP14-Pad1)") (class "Default")
      (node (ref "JP14") (pin "1") (pinfunction "1_1") (pintype "passive"))
      (node (ref "R14") (pin "2") (pinfunction "2_2") (pintype "passive"))
    )
    (net (code "49") (name "Net-(JP15-Pad1)") (class "Default")
      (node (ref "JP15") (pin "1") (pinfunction "1_1") (pintype "passive"))
      (node (ref "R15") (pin "2") (pinfunction "2_2") (pintype "passive"))
    )
    (net (code "50") (name "Net-(JP16-Pad1)") (class "Default")
      (node (ref "JP16") (pin "1") (pinfunction "1_1") (pintype "passive"))
      (node (ref "R16") (pin "2") (pinfunction "2_2") (pintype "passive"))
    )
    (net (code "51") (name "Net-(T1-D)") (class "Default")
      (node (ref "R1") (pin "1") (pinfunction "1_1") (pintype "passive"))
      (node (ref "T1") (pin "1") (pinfunction "D_1") (pintype "passive"))
    )
    (net (code "52") (name "Net-(T2-D)") (class "Default")
      (node (ref "R2") (pin "1") (pinfunction "1_1") (pintype "passive"))
      (node (ref "T2") (pin "1") (pinfunction "D_1") (pintype "passive"))
    )
    (net (code "53") (name "Net-(T3-D)") (class "Default")
      (node (ref "R3") (pin "1") (pinfunction "1_1") (pintype "passive"))
      (node (ref "T3") (pin "1") (pinfunction "D_1") (pintype "passive"))
    )
    (net (code "54") (name "Net-(T4-D)") (class "Default")
      (node (ref "R4") (pin "1") (pinfunction "1_1") (pintype "passive"))
      (node (ref "T4") (pin "1") (pinfunction "D_1") (pintype "passive"))
    )
    (net (code "55") (name "Net-(T5-D)") (class "Default")
      (node (ref "R5") (pin "1") (pinfunction "1_1") (pintype "passive"))
      (node (ref "T5") (pin "1") (pinfunction "D_1") (pintype "passive"))
    )
    (net (code "56") (name "Net-(T6-D)") (class "Default")
      (node (ref "R6") (pin "1") (pinfunction "1_1") (pintype "passive"))
      (node (ref "T6") (pin "1") (pinfunction "D_1") (pintype "passive"))
    )
    (net (code "57") (name "Net-(T7-D)") (class "Default")
      (node (ref "R7") (pin "1") (pinfunction "1_1") (pintype "passive"))
      (node (ref "T7") (pin "1") (pinfunction "D_1") (pintype "passive"))
    )
    (net (code "58") (name "Net-(T8-D)") (class "Default")
      (node (ref "R8") (pin "1") (pinfunction "1_1") (pintype "passive"))
      (node (ref "T8") (pin "1") (pinfunction "D_1") (pintype "passive"))
    )
    (net (code "59") (name "Net-(T9-D)") (class "Default")
      (node (ref "R9") (pin "1") (pinfunction "1_1") (pintype "passive"))
      (node (ref "T9") (pin "1") (pinfunction "D_1") (pintype "passive"))
    )
    (net (code "60") (name "Net-(T10-D)") (class "Default")
      (node (ref "R10") (pin "1") (pinfunction "1_1") (pintype "passive"))
      (node (ref "T10") (pin "1") (pinfunction "D_1") (pintype "passive"))
    )
    (net (code "61") (name "Net-(T11-D)") (class "Default")
      (node (ref "R11") (pin "1") (pinfunction "1_1") (pintype "passive"))
      (node (ref "T11") (pin "1") (pinfunction "D_1") (pintype "passive"))
    )
    (net (code "62") (name "Net-(T12-D)") (class "Default")
      (node (ref "R12") (pin "1") (pinfunction "1_1") (pintype "passive"))
      (node (ref "T12") (pin "1") (pinfunction "D_1") (pintype "passive"))
    )
    (net (code "63") (name "Net-(T13-D)") (class "Default")
      (node (ref "R13") (pin "1") (pinfunction "1_1") (pintype "passive"))
      (node (ref "T13") (pin "1") (pinfunction "D_1") (pintype "passive"))
    )
    (net (code "64") (name "Net-(T14-D)") (class "Default")
      (node (ref "R14") (pin "1") (pinfunction "1_1") (pintype "passive"))
      (node (ref "T14") (pin "1") (pinfunction "D_1") (pintype "passive"))
    )
    (net (code "65") (name "Net-(T15-D)") (class "Default")
      (node (ref "R15") (pin "1") (pinfunction "1_1") (pintype "passive"))
      (node (ref "T15") (pin "1") (pinfunction "D_1") (pintype "passive"))
    )
    (net (code "66") (name "Net-(T16-D)") (class "Default")
      (node (ref "R16") (pin "1") (pinfunction "1_1") (pintype "passive"))
      (node (ref "T16") (pin "1") (pinfunction "D_1") (pintype "passive"))
    )
    (net (code "67") (name "Net-(T17A-D)") (class "Default")
      (node (ref "R25") (pin "1") (pinfunction "1_1") (pintype "passive"))
      (node (ref "T17") (pin "6") (pinfunction "D_6") (pintype "passive"))
    )
    (net (code "68") (name "Net-(T17B-D)") (class "Default")
      (node (ref "JP17") (pin "1") (pinfunction "1_1") (pintype "passive"))
      (node (ref "T17") (pin "4") (pinfunction "D_4") (pintype "passive"))
    )
    (net (code "69") (name "Net-(T17B-G)") (class "Default")
      (node (ref "R17") (pin "1") (pinfunction "1_1") (pintype "passive"))
      (node (ref "R25") (pin "2") (pinfunction "2_2") (pintype "passive"))
      (node (ref "T17") (pin "3") (pinfunction "G_3") (pintype "passive"))
    )
    (net (code "70") (name "Net-(T18A-D)") (class "Default")
      (node (ref "R26") (pin "1") (pinfunction "1_1") (pintype "passive"))
      (node (ref "T18") (pin "6") (pinfunction "D_6") (pintype "passive"))
    )
    (net (code "71") (name "Net-(T18B-D)") (class "Default")
      (node (ref "JP18") (pin "1") (pinfunction "1_1") (pintype "passive"))
      (node (ref "T18") (pin "4") (pinfunction "D_4") (pintype "passive"))
    )
    (net (code "72") (name "Net-(T18B-G)") (class "Default")
      (node (ref "R18") (pin "1") (pinfunction "1_1") (pintype "passive"))
      (node (ref "R26") (pin "2") (pinfunction "2_2") (pintype "passive"))
      (node (ref "T18") (pin "3") (pinfunction "G_3") (pintype "passive"))
    )
    (net (code "73") (name "Net-(T19A-D)") (class "Default")
      (node (ref "R27") (pin "1") (pinfunction "1_1") (pintype "passive"))
      (node (ref "T19") (pin "6") (pinfunction "D_6") (pintype "passive"))
    )
    (net (code "74") (name "Net-(T19B-D)") (class "Default")
      (node (ref "JP19") (pin "1") (pinfunction "1_1") (pintype "passive"))
      (node (ref "T19") (pin "4") (pinfunction "D_4") (pintype "passive"))
    )
    (net (code "75") (name "Net-(T19B-G)") (class "Default")
      (node (ref "R19") (pin "1") (pinfunction "1_1") (pintype "passive"))
      (node (ref "R27") (pin "2") (pinfunction "2_2") (pintype "passive"))
      (node (ref "T19") (pin "3") (pinfunction "G_3") (pintype "passive"))
    )
    (net (code "76") (name "Net-(T20A-D)") (class "Default")
      (node (ref "R28") (pin "1") (pinfunction "1_1") (pintype "passive"))
      (node (ref "T20") (pin "6") (pinfunction "D_6") (pintype "passive"))
    )
    (net (code "77") (name "Net-(T20B-D)") (class "Default")
      (node (ref "JP20") (pin "1") (pinfunction "1_1") (pintype "passive"))
      (node (ref "T20") (pin "4") (pinfunction "D_4") (pintype "passive"))
    )
    (net (code "78") (name "Net-(T20B-G)") (class "Default")
      (node (ref "R20") (pin "1") (pinfunction "1_1") (pintype "passive"))
      (node (ref "R28") (pin "2") (pinfunction "2_2") (pintype "passive"))
      (node (ref "T20") (pin "3") (pinfunction "G_3") (pintype "passive"))
    )
    (net (code "79") (name "Net-(T21A-D)") (class "Default")
      (node (ref "R29") (pin "1") (pinfunction "1_1") (pintype "passive"))
      (node (ref "T21") (pin "6") (pinfunction "D_6") (pintype "passive"))
    )
    (net (code "80") (name "Net-(T21B-D)") (class "Default")
      (node (ref "JP21") (pin "1") (pinfunction "1_1") (pintype "passive"))
      (node (ref "T21") (pin "4") (pinfunction "D_4") (pintype "passive"))
    )
    (net (code "81") (name "Net-(T21B-G)") (class "Default")
      (node (ref "R21") (pin "1") (pinfunction "1_1") (pintype "passive"))
      (node (ref "R29") (pin "2") (pinfunction "2_2") (pintype "passive"))
      (node (ref "T21") (pin "3") (pinfunction "G_3") (pintype "passive"))
    )
    (net (code "82") (name "Net-(T22A-D)") (class "Default")
      (node (ref "R30") (pin "1") (pinfunction "1_1") (pintype "passive"))
      (node (ref "T22") (pin "6") (pinfunction "D_6") (pintype "passive"))
    )
    (net (code "83") (name "Net-(T22B-D)") (class "Default")
      (node (ref "JP22") (pin "1") (pinfunction "1_1") (pintype "passive"))
      (node (ref "T22") (pin "4") (pinfunction "D_4") (pintype "passive"))
    )
    (net (code "84") (name "Net-(T22B-G)") (class "Default")
      (node (ref "R22") (pin "1") (pinfunction "1_1") (pintype "passive"))
      (node (ref "R30") (pin "2") (pinfunction "2_2") (pintype "passive"))
      (node (ref "T22") (pin "3") (pinfunction "G_3") (pintype "passive"))
    )
    (net (code "85") (name "Net-(T23A-D)") (class "Default")
      (node (ref "R31") (pin "1") (pinfunction "1_1") (pintype "passive"))
      (node (ref "T23") (pin "6") (pinfunction "D_6") (pintype "passive"))
    )
    (net (code "86") (name "Net-(T23B-D)") (class "Default")
      (node (ref "JP23") (pin "1") (pinfunction "1_1") (pintype "passive"))
      (node (ref "T23") (pin "4") (pinfunction "D_4") (pintype "passive"))
    )
    (net (code "87") (name "Net-(T23B-G)") (class "Default")
      (node (ref "R23") (pin "1") (pinfunction "1_1") (pintype "passive"))
      (node (ref "R31") (pin "2") (pinfunction "2_2") (pintype "passive"))
      (node (ref "T23") (pin "3") (pinfunction "G_3") (pintype "passive"))
    )
    (net (code "88") (name "Net-(T24A-D)") (class "Default")
      (node (ref "R32") (pin "1") (pinfunction "1_1") (pintype "passive"))
      (node (ref "T24") (pin "6") (pinfunction "D_6") (pintype "passive"))
    )
    (net (code "89") (name "Net-(T24B-D)") (class "Default")
      (node (ref "JP24") (pin "1") (pinfunction "1_1") (pintype "passive"))
      (node (ref "T24") (pin "4") (pinfunction "D_4") (pintype "passive"))
    )
    (net (code "90") (name "Net-(T24B-G)") (class "Default")
      (node (ref "R24") (pin "1") (pinfunction "1_1") (pintype "passive"))
      (node (ref "R32") (pin "2") (pinfunction "2_2") (pintype "passive"))
      (node (ref "T24") (pin "3") (pinfunction "G_3") (pintype "passive"))
    )
    (net (code "91") (name "Net-(U1-NRST{slash}SBWTDIO)") (class "Default")
      (node (ref "JP25") (pin "5") (pinfunction "5_5") (pintype "passive"))
      (node (ref "U1") (pin "16") (pinfunction "NRST/SBWTDIO_16") (pintype "bidirectional"))
    )
    (net (code "92") (name "Net-(U1-P1.1)") (class "Default")
      (node (ref "JP25") (pin "3") (pinfunction "3_3") (pintype "passive"))
      (node (ref "U1") (pin "3") (pinfunction "P1.1_3") (pintype "bidirectional"))
    )
    (net (code "93") (name "Net-(U1-P1.2)") (class "Default")
      (node (ref "JP25") (pin "2") (pinfunction "2_2") (pintype "passive"))
      (node (ref "U1") (pin "4") (pinfunction "P1.2_4") (pintype "bidirectional"))
    )
    (net (code "94") (name "Net-(U1-SBWTCK)") (class "Default")
      (node (ref "JP25") (pin "4") (pinfunction "4_4") (pintype "passive"))
      (node (ref "U1") (pin "17") (pinfunction "SBWTCK_17") (pintype "bidirectional"))
    )
    (net (code "95") (name "unconnected-(IC4A-QH*-Pad9)") (class "Default")
      (node (ref "IC4") (pin "9") (pinfunction "QH*_9") (pintype "tri_state"))
    )
    (net (code "96") (name "unconnected-(U1-P1.0-Pad2)") (class "Default")
      (node (ref "U1") (pin "2") (pinfunction "P1.0_2") (pintype "bidirectional"))
    )
    (net (code "97") (name "unconnected-(U1-P1.3-Pad5)") (class "Default")
      (node (ref "U1") (pin "5") (pinfunction "P1.3_5") (pintype "bidirectional"))
    )
    (net (code "98") (name "unconnected-(U1-P1.4-Pad6)") (class "Default")
      (node (ref "U1") (pin "6") (pinfunction "P1.4_6") (pintype "bidirectional"))
    )
    (net (code "99") (name "unconnected-(U1-P1.5-Pad7)") (class "Default")
      (node (ref "U1") (pin "7") (pinfunction "P1.5_7") (pintype "bidirectional"))
    )
    (net (code "100") (name "unconnected-(U1-P1.7-Pad15)") (class "Default")
      (node (ref "U1") (pin "15") (pinfunction "P1.7_15") (pintype "bidirectional"))
    )
    (net (code "101") (name "unconnected-(U1-P2.0-Pad8)") (class "Default")
      (node (ref "U1") (pin "8") (pinfunction "P2.0_8") (pintype "bidirectional"))
    )
    (net (code "102") (name "unconnected-(U1-P2.2-Pad10)") (class "Default")
      (node (ref "U1") (pin "10") (pinfunction "P2.2_10") (pintype "bidirectional"))
    )
    (net (code "103") (name "unconnected-(U1-P2.6{slash}XIN-Pad18)") (class "Default")
      (node (ref "U1") (pin "18") (pinfunction "P2.6/XIN_18") (pintype "bidirectional"))
    )
    (net (code "104") (name "unconnected-(U1-P2.7{slash}XOUT-Pad19)") (class "Default")
      (node (ref "U1") (pin "19") (pinfunction "P2.7/XOUT_19") (pintype "bidirectional"))
    )
  )
)
